# USB-PHY.net
KiCad netlist of a schematic drawn in Altium Designer
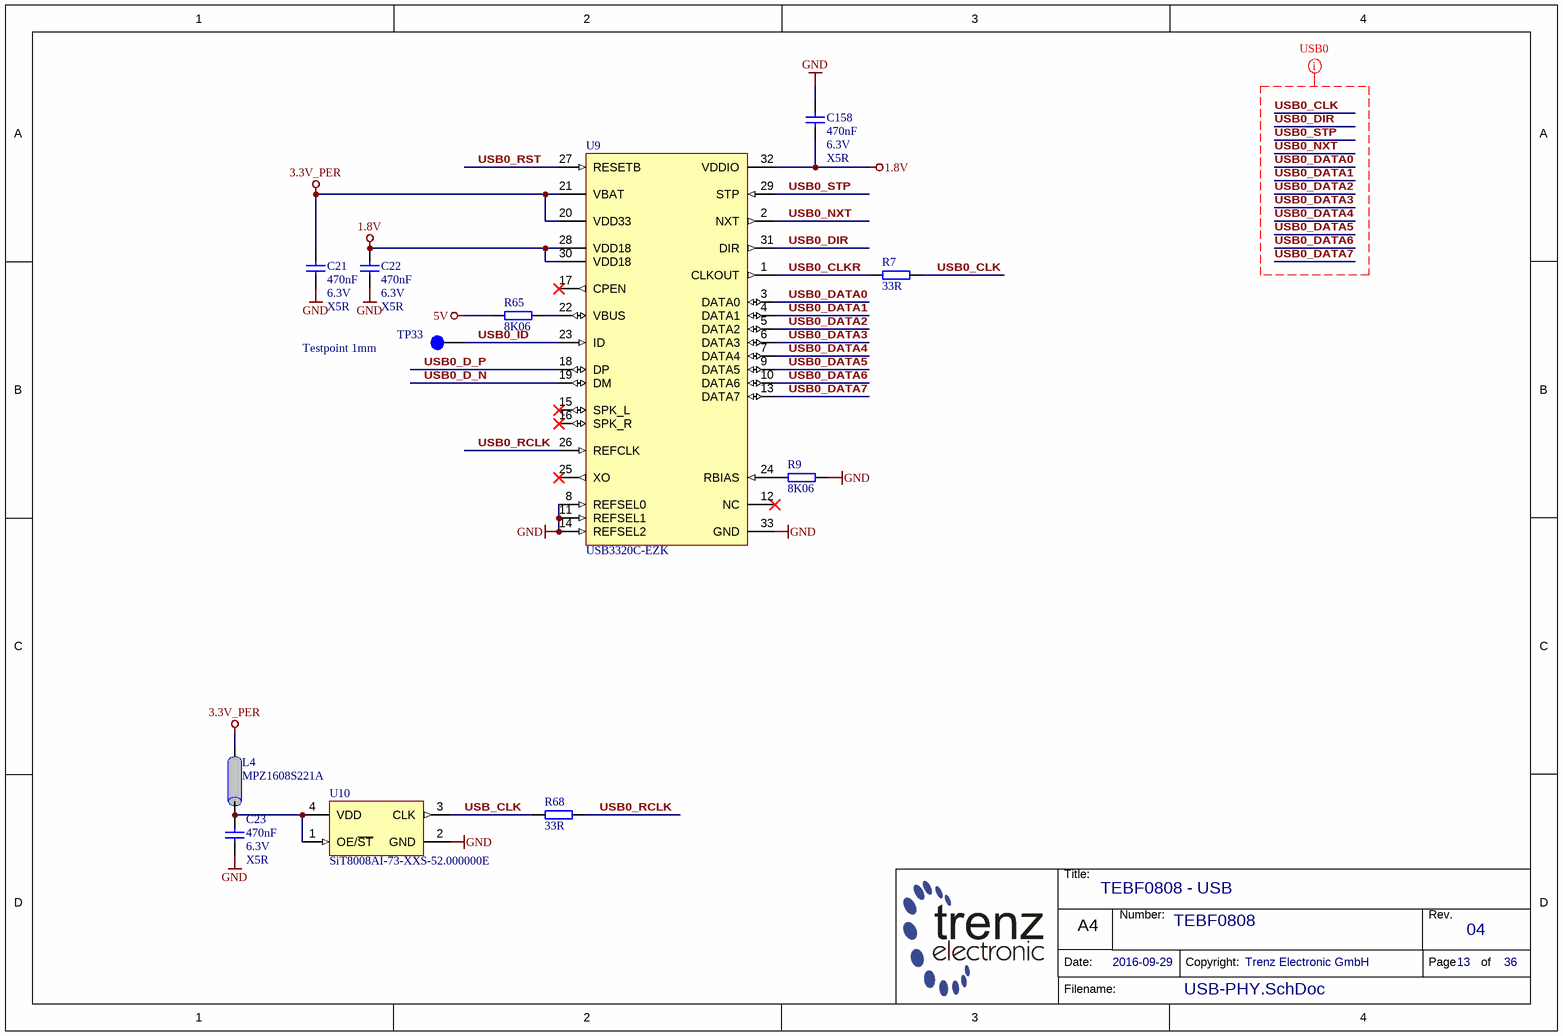
[diagram p0: USB-PHY.SchDoc]

(export (version "E")
  (design (tool "Eeschema 10.0.6"))
  (components
    (comp (ref "C21")
      (value "470nF")
      (footprint "CAPC1005X55N")
      (description "KON 470nF 6,3V X5R SMD")
      (fields (field (name "VOLTAGE") "6.3V") (field (name "TECHNOLOGY") "X5R"))
      (libsource (lib "TE") (part "CAP-NP"))
    )
    (comp (ref "C22")
      (value "470nF")
      (footprint "CAPC1005X55N")
      (description "KON 470nF 6,3V X5R SMD")
      (fields (field (name "VOLTAGE") "6.3V") (field (name "TECHNOLOGY") "X5R"))
      (libsource (lib "TE") (part "CAP-NP"))
    )
    (comp (ref "C23")
      (value "470nF")
      (footprint "CAPC1005X55N")
      (description "KON 470nF 6,3V X5R SMD")
      (fields (field (name "VOLTAGE") "6.3V") (field (name "TECHNOLOGY") "X5R"))
      (libsource (lib "TE") (part "CAP-NP"))
    )
    (comp (ref "C158")
      (value "470nF")
      (footprint "CAPC1005X55N")
      (description "KON 470nF 6,3V X5R SMD")
      (fields (field (name "VOLTAGE") "6.3V") (field (name "TECHNOLOGY") "X5R"))
      (libsource (lib "TE") (part "CAP-NP"))
    )
    (comp (ref "L4")
      (value "MPZ1608S221A")
      (footprint "INDC1608X95N")
      (description "Ferritdurchführung MPZ1608S221A")
      (libsource (lib "TE") (part "Ferritperle"))
    )
    (comp (ref "R7")
      (value "33R")
      (footprint "RESC1005X40N")
      (description "WID SMD 33R 1% 0,063W")
      (fields (field (name "TOLERANCE") "1%"))
      (libsource (lib "TE") (part "RES"))
    )
    (comp (ref "R9")
      (value "8K06")
      (footprint "RESC1005X40N")
      (description "WID SMD 8K06 1% 0,063W")
      (fields (field (name "TOLERANCE") "1%"))
      (libsource (lib "TE") (part "RES"))
    )
    (comp (ref "R65")
      (value "8K06")
      (footprint "RESC1005X40N")
      (description "WID SMD 8K06 1% 0,063W")
      (fields (field (name "TOLERANCE") "1%"))
      (libsource (lib "TE") (part "RES"))
    )
    (comp (ref "R68")
      (value "33R")
      (footprint "RESC1005X40N")
      (description "WID SMD 33R 1% 0,063W")
      (fields (field (name "TOLERANCE") "1%"))
      (libsource (lib "TE") (part "RES"))
    )
    (comp (ref "TP33") (value "Testpoint 1mm") (footprint "TP_1mm") (libsource (lib "TE") (part "TP")))
    (comp (ref "U9")
      (value "USB3320C-EZK")
      (footprint "QFN50P500X500X100-33N-345")
      (libsource (lib "TE") (part "USB3320"))
    )
    (comp (ref "U10")
      (value "SiT8008AI-73-XXS-52.000000E")
      (footprint "2016")
      (description "SiT8008AI-73-XXS-52.000000E MEMS Oszillator 52MHz")
      (libsource (lib "TE") (part "SiT8103"))
    )
  )
  (nets
    (net (code "1") (name "/USB0_CLK") (class "Default")
      (node (ref "R7") (pin "2") (pinfunction "2_2") (pintype "passive"))
    )
    (net (code "2") (name "/USB0_CLKR") (class "Default")
      (node (ref "R7") (pin "1") (pinfunction "1_1") (pintype "passive"))
      (node (ref "U9") (pin "1") (pinfunction "CLKOUT_1") (pintype "output"))
    )
    (net (code "3") (name "/USB0_DATA0") (class "Default")
      (node (ref "U9") (pin "3") (pinfunction "DATA0_3") (pintype "bidirectional"))
    )
    (net (code "4") (name "/USB0_DATA1") (class "Default")
      (node (ref "U9") (pin "4") (pinfunction "DATA1_4") (pintype "bidirectional"))
    )
    (net (code "5") (name "/USB0_DATA2") (class "Default")
      (node (ref "U9") (pin "5") (pinfunction "DATA2_5") (pintype "bidirectional"))
    )
    (net (code "6") (name "/USB0_DATA3") (class "Default")
      (node (ref "U9") (pin "6") (pinfunction "DATA3_6") (pintype "bidirectional"))
    )
    (net (code "7") (name "/USB0_DATA4") (class "Default")
      (node (ref "U9") (pin "7") (pinfunction "DATA4_7") (pintype "bidirectional"))
    )
    (net (code "8") (name "/USB0_DATA5") (class "Default")
      (node (ref "U9") (pin "9") (pinfunction "DATA5_9") (pintype "bidirectional"))
    )
    (net (code "9") (name "/USB0_DATA6") (class "Default")
      (node (ref "U9") (pin "10") (pinfunction "DATA6_10") (pintype "bidirectional"))
    )
    (net (code "10") (name "/USB0_DATA7") (class "Default")
      (node (ref "U9") (pin "13") (pinfunction "DATA7_13") (pintype "bidirectional"))
    )
    (net (code "11") (name "/USB0_DIR") (class "Default")
      (node (ref "U9") (pin "31") (pinfunction "DIR_31") (pintype "output"))
    )
    (net (code "12") (name "/USB0_D_N") (class "Default")
      (node (ref "U9") (pin "19") (pinfunction "DM_19") (pintype "bidirectional"))
    )
    (net (code "13") (name "/USB0_D_P") (class "Default")
      (node (ref "U9") (pin "18") (pinfunction "DP_18") (pintype "bidirectional"))
    )
    (net (code "14") (name "/USB0_ID") (class "Default")
      (node (ref "TP33") (pin "1") (pintype "passive"))
      (node (ref "U9") (pin "23") (pinfunction "ID_23") (pintype "input"))
    )
    (net (code "15") (name "/USB0_NXT") (class "Default")
      (node (ref "U9") (pin "2") (pinfunction "NXT_2") (pintype "output"))
    )
    (net (code "16") (name "/USB0_RCLK") (class "Default")
      (node (ref "R68") (pin "2") (pinfunction "2_2") (pintype "passive"))
      (node (ref "U9") (pin "26") (pinfunction "REFCLK_26") (pintype "input"))
    )
    (net (code "17") (name "/USB0_RST") (class "Default")
      (node (ref "U9") (pin "27") (pinfunction "RESETB_27") (pintype "input"))
    )
    (net (code "18") (name "/USB0_STP") (class "Default")
      (node (ref "U9") (pin "29") (pinfunction "STP_29") (pintype "input"))
    )
    (net (code "19") (name "/USB_CLK") (class "Default")
      (node (ref "R68") (pin "1") (pinfunction "1_1") (pintype "passive"))
      (node (ref "U10") (pin "3") (pinfunction "CLK_3") (pintype "output"))
    )
    (net (code "20") (name "1.8V") (class "Default")
      (node (ref "C158") (pin "2") (pinfunction "2_2") (pintype "passive"))
      (node (ref "C22") (pin "1") (pinfunction "1_1") (pintype "passive"))
      (node (ref "U9") (pin "28") (pinfunction "VDD18_28") (pintype "power_in"))
      (node (ref "U9") (pin "30") (pinfunction "VDD18_30") (pintype "power_in"))
      (node (ref "U9") (pin "32") (pinfunction "VDDIO_32") (pintype "power_in"))
    )
    (net (code "21") (name "3.3V_PER") (class "Default")
      (node (ref "C21") (pin "1") (pinfunction "1_1") (pintype "passive"))
      (node (ref "L4") (pin "1") (pinfunction "1_1") (pintype "passive"))
      (node (ref "U9") (pin "20") (pinfunction "VDD33_20") (pintype "power_in"))
      (node (ref "U9") (pin "21") (pinfunction "VBAT_21") (pintype "power_in"))
    )
    (net (code "22") (name "5V") (class "Default")
      (node (ref "R65") (pin "1") (pinfunction "1_1") (pintype "passive"))
    )
    (net (code "23") (name "GND") (class "Default")
      (node (ref "C158") (pin "1") (pinfunction "1_1") (pintype "passive"))
      (node (ref "C21") (pin "2") (pinfunction "2_2") (pintype "passive"))
      (node (ref "C22") (pin "2") (pinfunction "2_2") (pintype "passive"))
      (node (ref "C23") (pin "2") (pinfunction "2_2") (pintype "passive"))
      (node (ref "R9") (pin "2") (pinfunction "2_2") (pintype "passive"))
      (node (ref "U10") (pin "2") (pinfunction "GND_2") (pintype "power_in"))
      (node (ref "U9") (pin "11") (pinfunction "REFSEL1_11") (pintype "input"))
      (node (ref "U9") (pin "14") (pinfunction "REFSEL2_14") (pintype "input"))
      (node (ref "U9") (pin "33") (pinfunction "GND_33") (pintype "power_in"))
      (node (ref "U9") (pin "8") (pinfunction "REFSEL0_8") (pintype "input"))
    )
    (net (code "24") (name "Net-(U9-RBIAS)") (class "Default")
      (node (ref "R9") (pin "1") (pinfunction "1_1") (pintype "passive"))
      (node (ref "U9") (pin "24") (pinfunction "RBIAS_24") (pintype "input"))
    )
    (net (code "25") (name "Net-(U9-VBUS)") (class "Default")
      (node (ref "R65") (pin "2") (pinfunction "2_2") (pintype "passive"))
      (node (ref "U9") (pin "22") (pinfunction "VBUS_22") (pintype "bidirectional"))
    )
    (net (code "26") (name "Net-(U10-OE{slash}~{ST})") (class "Default")
      (node (ref "C23") (pin "1") (pinfunction "1_1") (pintype "passive"))
      (node (ref "L4") (pin "2") (pinfunction "2_2") (pintype "passive"))
      (node (ref "U10") (pin "1") (pinfunction "OE/~{ST}_1") (pintype "input"))
      (node (ref "U10") (pin "4") (pinfunction "VDD_4") (pintype "power_in"))
    )
    (net (code "27") (name "unconnected-(U9-CPEN-Pad17)") (class "Default")
      (node (ref "U9") (pin "17") (pinfunction "CPEN_17") (pintype "output+no_connect"))
    )
    (net (code "28") (name "unconnected-(U9-NC-Pad12)") (class "Default")
      (node (ref "U9") (pin "12") (pinfunction "NC_12") (pintype "passive+no_connect"))
    )
    (net (code "29") (name "unconnected-(U9-SPK_L-Pad15)") (class "Default")
      (node (ref "U9") (pin "15") (pinfunction "SPK_L_15") (pintype "bidirectional+no_connect"))
    )
    (net (code "30") (name "unconnected-(U9-SPK_R-Pad16)") (class "Default")
      (node (ref "U9") (pin "16") (pinfunction "SPK_R_16") (pintype "bidirectional+no_connect"))
    )
    (net (code "31") (name "unconnected-(U9-XO-Pad25)") (class "Default")
      (node (ref "U9") (pin "25") (pinfunction "XO_25") (pintype "output+no_connect"))
    )
  )
)
